# OdomEncoders.net
KiCad netlist of a schematic drawn in Altium Designer
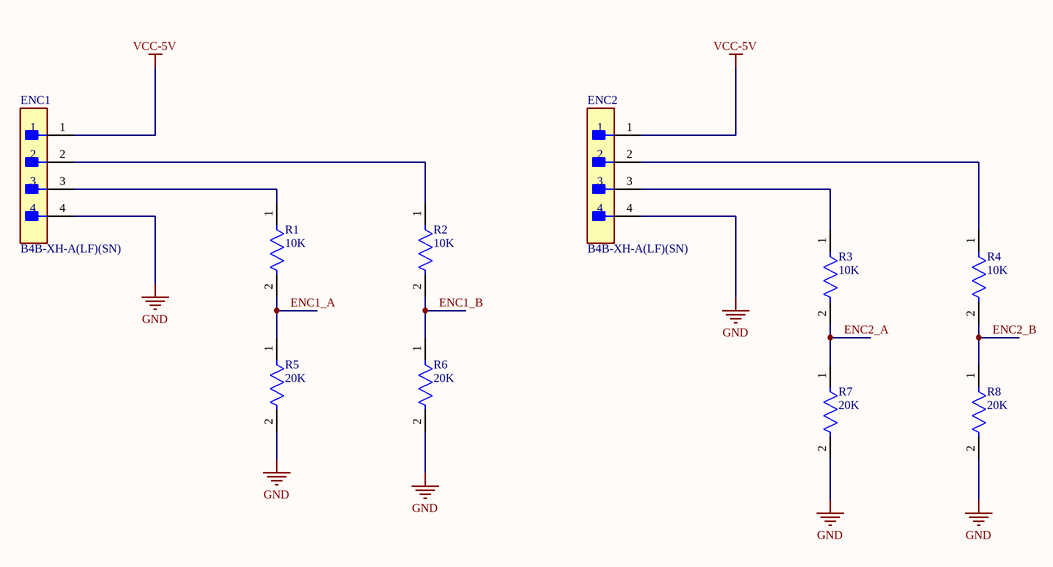
[diagram p0: OdomEncoders.SchDoc]

(export (version "E")
  (design (tool "Eeschema 10.0.6"))
  (components
    (comp (ref "ENC1")
      (value "B4B-XH-A(LF)(SN)")
      (footprint "FP-B4B-XH-A_LF_SN-MFG")
      (description "CONN HEADER VERT 4POS 2.5MM")
      (libsource (lib "Altium Content Vault") (part "299a8cea1bdcbc3624fe62c390fa72c"))
    )
    (comp (ref "ENC2")
      (value "B4B-XH-A(LF)(SN)")
      (footprint "FP-B4B-XH-A_LF_SN-MFG")
      (description "CONN HEADER VERT 4POS 2.5MM")
      (libsource (lib "Altium Content Vault") (part "299a8cea1bdcbc3624fe62c390fa72c"))
    )
    (comp (ref "R1")
      (value "10K")
      (footprint "FP-RC0603-0_55-IPC_C")
      (description "RES 10K OHM 1% 1/10W 0603")
      (fields (field (name "TOLERANCE") "1%"))
      (libsource (lib "Altium Content Vault") (part "1029c3af85768c4190bb7ad29bc67b5"))
    )
    (comp (ref "R2")
      (value "10K")
      (footprint "FP-RC0603-0_55-IPC_C")
      (description "RES 10K OHM 1% 1/10W 0603")
      (fields (field (name "TOLERANCE") "1%"))
      (libsource (lib "Altium Content Vault") (part "1029c3af85768c4190bb7ad29bc67b5"))
    )
    (comp (ref "R3")
      (value "10K")
      (footprint "FP-RC0603-0_55-IPC_C")
      (description "RES 10K OHM 1% 1/10W 0603")
      (fields (field (name "TOLERANCE") "1%"))
      (libsource (lib "Altium Content Vault") (part "1029c3af85768c4190bb7ad29bc67b5"))
    )
    (comp (ref "R4")
      (value "10K")
      (footprint "FP-RC0603-0_55-IPC_C")
      (description "RES 10K OHM 1% 1/10W 0603")
      (fields (field (name "TOLERANCE") "1%"))
      (libsource (lib "Altium Content Vault") (part "1029c3af85768c4190bb7ad29bc67b5"))
    )
    (comp (ref "R5")
      (value "20K")
      (footprint "FP-RC0603-0_55-IPC_C")
      (description "RES 20K OHM 1% 1/10W 0603")
      (fields (field (name "TOLERANCE") "1%"))
      (libsource (lib "Altium Content Vault") (part "1029c3af85768c4190bb7ad29bc67b5"))
    )
    (comp (ref "R6")
      (value "20K")
      (footprint "FP-RC0603-0_55-IPC_C")
      (description "RES 20K OHM 1% 1/10W 0603")
      (fields (field (name "TOLERANCE") "1%"))
      (libsource (lib "Altium Content Vault") (part "1029c3af85768c4190bb7ad29bc67b5"))
    )
    (comp (ref "R7")
      (value "20K")
      (footprint "FP-RC0603-0_55-IPC_C")
      (description "RES 20K OHM 1% 1/10W 0603")
      (fields (field (name "TOLERANCE") "1%"))
      (libsource (lib "Altium Content Vault") (part "1029c3af85768c4190bb7ad29bc67b5"))
    )
    (comp (ref "R8")
      (value "20K")
      (footprint "FP-RC0603-0_55-IPC_C")
      (description "RES 20K OHM 1% 1/10W 0603")
      (fields (field (name "TOLERANCE") "1%"))
      (libsource (lib "Altium Content Vault") (part "1029c3af85768c4190bb7ad29bc67b5"))
    )
  )
  (nets
    (net (code "1") (name "/ENC1_A") (class "Default")
      (node (ref "R1") (pin "2") (pinfunction "2_2") (pintype "passive"))
      (node (ref "R5") (pin "1") (pinfunction "1_1") (pintype "passive"))
    )
    (net (code "2") (name "/ENC1_B") (class "Default")
      (node (ref "R2") (pin "2") (pinfunction "2_2") (pintype "passive"))
      (node (ref "R6") (pin "1") (pinfunction "1_1") (pintype "passive"))
    )
    (net (code "3") (name "/ENC2_A") (class "Default")
      (node (ref "R3") (pin "2") (pinfunction "2_2") (pintype "passive"))
      (node (ref "R7") (pin "1") (pinfunction "1_1") (pintype "passive"))
    )
    (net (code "4") (name "/ENC2_B") (class "Default")
      (node (ref "R4") (pin "2") (pinfunction "2_2") (pintype "passive"))
      (node (ref "R8") (pin "1") (pinfunction "1_1") (pintype "passive"))
    )
    (net (code "5") (name "GND") (class "Default")
      (node (ref "ENC1") (pin "4") (pinfunction "4_4") (pintype "passive"))
      (node (ref "ENC2") (pin "4") (pinfunction "4_4") (pintype "passive"))
      (node (ref "R5") (pin "2") (pinfunction "2_2") (pintype "passive"))
      (node (ref "R6") (pin "2") (pinfunction "2_2") (pintype "passive"))
      (node (ref "R7") (pin "2") (pinfunction "2_2") (pintype "passive"))
      (node (ref "R8") (pin "2") (pinfunction "2_2") (pintype "passive"))
    )
    (net (code "6") (name "Net-(ENC1-Pad2)") (class "Default")
      (node (ref "ENC1") (pin "2") (pinfunction "2_2") (pintype "passive"))
      (node (ref "R2") (pin "1") (pinfunction "1_1") (pintype "passive"))
    )
    (net (code "7") (name "Net-(ENC1-Pad3)") (class "Default")
      (node (ref "ENC1") (pin "3") (pinfunction "3_3") (pintype "passive"))
      (node (ref "R1") (pin "1") (pinfunction "1_1") (pintype "passive"))
    )
    (net (code "8") (name "Net-(ENC2-Pad2)") (class "Default")
      (node (ref "ENC2") (pin "2") (pinfunction "2_2") (pintype "passive"))
      (node (ref "R4") (pin "1") (pinfunction "1_1") (pintype "passive"))
    )
    (net (code "9") (name "Net-(ENC2-Pad3)") (class "Default")
      (node (ref "ENC2") (pin "3") (pinfunction "3_3") (pintype "passive"))
      (node (ref "R3") (pin "1") (pinfunction "1_1") (pintype "passive"))
    )
    (net (code "10") (name "VCC-5V") (class "Default")
      (node (ref "ENC1") (pin "1") (pinfunction "1_1") (pintype "passive"))
      (node (ref "ENC2") (pin "1") (pinfunction "1_1") (pintype "passive"))
    )
  )
)
